# Capacitor_Isolated_Supply.net
KiCad netlist of a schematic drawn in Altium Designer
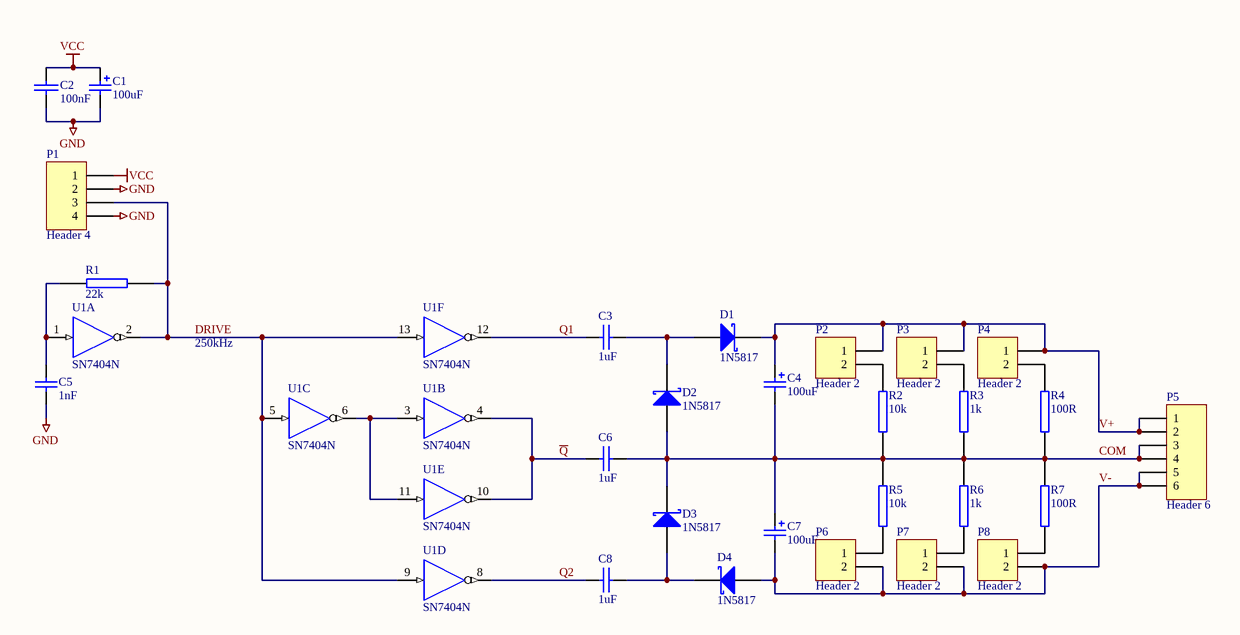
[diagram p0: Capacitor Isolated Supply (Bipolar).SchDoc]

(export (version "E")
  (design (tool "Eeschema 10.0.6"))
  (components
    (comp (ref "C1")
      (value "100uF")
      (footprint "RB5-10.5")
      (description "CAPACITOR POLARISED TAG B CASE")
      (fields
        (field (name "MANUFACTURER") "Generic Components")
        (field (name "MOUSER PART NO.") "74-293D106X9020B8T")
      )
      (libsource (lib "Mi-Call Schematic") (part "Cap Pol"))
    )
    (comp (ref "C2")
      (value "100nF")
      (footprint "CAP (3D) - 0805")
      (description "CAPACITOR SMD 0603")
      (fields (field (name "MOUSER PART NO.") "81-GCM188R71C104KA7D") (field (name "MANUFACTURER") "Murata"))
      (libsource (lib "Mi-Call Schematic") (part "CAP"))
    )
    (comp (ref "C3")
      (value "1uF")
      (footprint "RES (3D) - 1210")
      (description "CAPACITOR SMD 0603")
      (fields (field (name "MOUSER PART NO.") "77-VJ1206V105MXATBC") (field (name "MANUFACTURER") "Vishay"))
      (libsource (lib "Mi-Call Schematic") (part "CAP"))
    )
    (comp (ref "C4")
      (value "100uF")
      (footprint "RB5-10.5")
      (description "CAPACITOR POLARISED TAG B CASE")
      (fields
        (field (name "MANUFACTURER") "Generic Components")
        (field (name "MOUSER PART NO.") "74-293D106X9020B8T")
      )
      (libsource (lib "Mi-Call Schematic") (part "Cap Pol"))
    )
    (comp (ref "C5")
      (value "1nF")
      (footprint "CAP (3D) - 0805")
      (description "Capacitor")
      (fields (field (name "Comment") "Cap") (field (name "PUBLISHER") "Altium Limited"))
      (libsource (lib "Miscellaneous Devices") (part "Cap"))
    )
    (comp (ref "C6")
      (value "1uF")
      (footprint "RES (3D) - 1210")
      (description "CAPACITOR SMD 0603")
      (fields (field (name "MOUSER PART NO.") "77-VJ1206V105MXATBC") (field (name "MANUFACTURER") "Vishay"))
      (libsource (lib "Mi-Call Schematic") (part "CAP"))
    )
    (comp (ref "C7")
      (value "100uF")
      (footprint "RB5-10.5")
      (description "CAPACITOR POLARISED TAG B CASE")
      (fields
        (field (name "MANUFACTURER") "Generic Components")
        (field (name "MOUSER PART NO.") "74-293D106X9020B8T")
      )
      (libsource (lib "Mi-Call Schematic") (part "Cap Pol"))
    )
    (comp (ref "C8")
      (value "1uF")
      (footprint "RES (3D) - 1210")
      (description "CAPACITOR SMD 0603")
      (fields (field (name "MOUSER PART NO.") "77-VJ1206V105MXATBC") (field (name "MANUFACTURER") "Vishay"))
      (libsource (lib "Mi-Call Schematic") (part "CAP"))
    )
    (comp (ref "D1")
      (value "1N5817")
      (footprint "DO-41")
      (description "Schottky Diode")
      (fields (field (name "PUBLISHER") "Altium Limited"))
      (libsource (lib "Miscellaneous Devices") (part "D Schottky"))
    )
    (comp (ref "D2")
      (value "1N5817")
      (footprint "DO-41")
      (description "Schottky Diode")
      (fields (field (name "PUBLISHER") "Altium Limited"))
      (libsource (lib "Miscellaneous Devices") (part "D Schottky"))
    )
    (comp (ref "D3")
      (value "1N5817")
      (footprint "DO-41")
      (description "Schottky Diode")
      (fields (field (name "PUBLISHER") "Altium Limited"))
      (libsource (lib "Miscellaneous Devices") (part "D Schottky"))
    )
    (comp (ref "D4")
      (value "1N5817")
      (footprint "DO-41")
      (description "Schottky Diode")
      (fields (field (name "PUBLISHER") "Altium Limited"))
      (libsource (lib "Miscellaneous Devices") (part "D Schottky"))
    )
    (comp (ref "P1")
      (value "Header 4")
      (footprint "HDR1X4")
      (description "Header, 4-Pin")
      (fields (field (name "PUBLISHER") "Altium Limited"))
      (libsource (lib "Miscellaneous Connectors") (part "Header 4"))
    )
    (comp (ref "P2")
      (value "Header 2")
      (footprint "HDR1X2")
      (description "Header, 2-Pin")
      (fields (field (name "PUBLISHER") "Altium Limited"))
      (libsource (lib "Miscellaneous Connectors") (part "Header 2"))
    )
    (comp (ref "P3")
      (value "Header 2")
      (footprint "HDR1X2")
      (description "Header, 2-Pin")
      (fields (field (name "PUBLISHER") "Altium Limited"))
      (libsource (lib "Miscellaneous Connectors") (part "Header 2"))
    )
    (comp (ref "P4")
      (value "Header 2")
      (footprint "HDR1X2")
      (description "Header, 2-Pin")
      (fields (field (name "PUBLISHER") "Altium Limited"))
      (libsource (lib "Miscellaneous Connectors") (part "Header 2"))
    )
    (comp (ref "P5")
      (value "Header 6")
      (footprint "HDR1X6")
      (description "Header, 6-Pin")
      (fields (field (name "PUBLISHER") "Altium Limited"))
      (libsource (lib "Miscellaneous Connectors") (part "Header 6"))
    )
    (comp (ref "P6")
      (value "Header 2")
      (footprint "HDR1X2")
      (description "Header, 2-Pin")
      (fields (field (name "PUBLISHER") "Altium Limited"))
      (libsource (lib "Miscellaneous Connectors") (part "Header 2"))
    )
    (comp (ref "P7")
      (value "Header 2")
      (footprint "HDR1X2")
      (description "Header, 2-Pin")
      (fields (field (name "PUBLISHER") "Altium Limited"))
      (libsource (lib "Miscellaneous Connectors") (part "Header 2"))
    )
    (comp (ref "P8")
      (value "Header 2")
      (footprint "HDR1X2")
      (description "Header, 2-Pin")
      (fields (field (name "PUBLISHER") "Altium Limited"))
      (libsource (lib "Miscellaneous Connectors") (part "Header 2"))
    )
    (comp (ref "R1")
      (value "22k")
      (footprint "RES (3D) - 0805")
      (description "RESISTOR SMD 0603 10k")
      (libsource (lib "NASCO Resistors") (part "RES SMD 0603 10k"))
    )
    (comp (ref "R2")
      (value "10k")
      (footprint "RES (3D) - 0805")
      (description "RESISTOR SMD 0603 10k")
      (libsource (lib "NASCO Resistors") (part "RES SMD 0603 10k"))
    )
    (comp (ref "R3")
      (value "1k")
      (footprint "RES (3D) - 0805")
      (description "RESISTOR SMD 0603 10k")
      (libsource (lib "NASCO Resistors") (part "RES SMD 0603 10k"))
    )
    (comp (ref "R4")
      (value "100R")
      (footprint "RES (3D) - 0805")
      (description "RESISTOR SMD 0603 10k")
      (libsource (lib "NASCO Resistors") (part "RES SMD 0603 10k"))
    )
    (comp (ref "R5")
      (value "10k")
      (footprint "RES (3D) - 0805")
      (description "RESISTOR SMD 0603 10k")
      (libsource (lib "NASCO Resistors") (part "RES SMD 0603 10k"))
    )
    (comp (ref "R6")
      (value "1k")
      (footprint "RES (3D) - 0805")
      (description "RESISTOR SMD 0603 10k")
      (libsource (lib "NASCO Resistors") (part "RES SMD 0603 10k"))
    )
    (comp (ref "R7")
      (value "100R")
      (footprint "RES (3D) - 0805")
      (description "RESISTOR SMD 0603 10k")
      (libsource (lib "NASCO Resistors") (part "RES SMD 0603 10k"))
    )
    (comp (ref "U1")
      (value "SN7404N")
      (footprint "N014")
      (description "Hex Inverter")
      (fields (field (name "PUBLISHER") "Altium Limited"))
      (libsource (lib "TI Logic Gate 1") (part "SN7404N"))
    )
  )
  (nets
    (net (code "1") (name "/COM") (class "Default")
      (node (ref "C4") (pin "2") (pinfunction "2_2") (pintype "passive"))
      (node (ref "C6") (pin "2") (pinfunction "2_2") (pintype "passive"))
      (node (ref "C7") (pin "1") (pinfunction "1_1") (pintype "passive"))
      (node (ref "D2") (pin "1") (pinfunction "A_1") (pintype "passive"))
      (node (ref "D3") (pin "2") (pinfunction "K_2") (pintype "passive"))
      (node (ref "P5") (pin "3") (pinfunction "3_3") (pintype "passive"))
      (node (ref "P5") (pin "4") (pinfunction "4_4") (pintype "passive"))
      (node (ref "R2") (pin "1") (pinfunction "1_1") (pintype "passive"))
      (node (ref "R3") (pin "1") (pinfunction "1_1") (pintype "passive"))
      (node (ref "R4") (pin "1") (pinfunction "1_1") (pintype "passive"))
      (node (ref "R5") (pin "2") (pinfunction "2_2") (pintype "passive"))
      (node (ref "R6") (pin "2") (pinfunction "2_2") (pintype "passive"))
      (node (ref "R7") (pin "2") (pinfunction "2_2") (pintype "passive"))
    )
    (net (code "2") (name "/DRIVE") (class "Default")
      (node (ref "P1") (pin "3") (pinfunction "3_3") (pintype "passive"))
      (node (ref "R1") (pin "1") (pinfunction "1_1") (pintype "passive"))
      (node (ref "U1") (pin "13") (pinfunction "A_13") (pintype "input"))
      (node (ref "U1") (pin "2") (pinfunction "Y_2") (pintype "output"))
      (node (ref "U1") (pin "5") (pinfunction "A_5") (pintype "input"))
      (node (ref "U1") (pin "9") (pinfunction "A_9") (pintype "input"))
    )
    (net (code "3") (name "/Q1") (class "Default")
      (node (ref "C3") (pin "1") (pinfunction "1_1") (pintype "passive"))
      (node (ref "U1") (pin "12") (pinfunction "Y_12") (pintype "output"))
    )
    (net (code "4") (name "/Q2") (class "Default")
      (node (ref "C8") (pin "1") (pinfunction "1_1") (pintype "passive"))
      (node (ref "U1") (pin "8") (pinfunction "Y_8") (pintype "output"))
    )
    (net (code "5") (name "/V+") (class "Default")
      (node (ref "C4") (pin "1") (pinfunction "1_1") (pintype "passive"))
      (node (ref "D1") (pin "2") (pinfunction "K_2") (pintype "passive"))
      (node (ref "P2") (pin "1") (pinfunction "1_1") (pintype "passive"))
      (node (ref "P3") (pin "1") (pinfunction "1_1") (pintype "passive"))
      (node (ref "P4") (pin "1") (pinfunction "1_1") (pintype "passive"))
      (node (ref "P5") (pin "1") (pinfunction "1_1") (pintype "passive"))
      (node (ref "P5") (pin "2") (pinfunction "2_2") (pintype "passive"))
    )
    (net (code "6") (name "/V-") (class "Default")
      (node (ref "C7") (pin "2") (pinfunction "2_2") (pintype "passive"))
      (node (ref "D4") (pin "1") (pinfunction "A_1") (pintype "passive"))
      (node (ref "P5") (pin "5") (pinfunction "5_5") (pintype "passive"))
      (node (ref "P5") (pin "6") (pinfunction "6_6") (pintype "passive"))
      (node (ref "P6") (pin "2") (pinfunction "2_2") (pintype "passive"))
      (node (ref "P7") (pin "2") (pinfunction "2_2") (pintype "passive"))
      (node (ref "P8") (pin "2") (pinfunction "2_2") (pintype "passive"))
    )
    (net (code "7") (name "/~{Q}") (class "Default")
      (node (ref "C6") (pin "1") (pinfunction "1_1") (pintype "passive"))
      (node (ref "U1") (pin "10") (pinfunction "Y_10") (pintype "output"))
      (node (ref "U1") (pin "4") (pinfunction "Y_4") (pintype "output"))
    )
    (net (code "8") (name "GND") (class "Default")
      (node (ref "C1") (pin "2") (pinfunction "2_2") (pintype "passive"))
      (node (ref "C2") (pin "2") (pinfunction "2_2") (pintype "passive"))
      (node (ref "C5") (pin "2") (pinfunction "2_2") (pintype "passive"))
      (node (ref "P1") (pin "2") (pinfunction "2_2") (pintype "passive"))
      (node (ref "P1") (pin "4") (pinfunction "4_4") (pintype "passive"))
      (node (ref "U1") (pin "7") (pinfunction "GND_7") (pintype "power_in"))
    )
    (net (code "9") (name "Net-(D1-A)") (class "Default")
      (node (ref "C3") (pin "2") (pinfunction "2_2") (pintype "passive"))
      (node (ref "D1") (pin "1") (pinfunction "A_1") (pintype "passive"))
      (node (ref "D2") (pin "2") (pinfunction "K_2") (pintype "passive"))
    )
    (net (code "10") (name "Net-(D3-A)") (class "Default")
      (node (ref "C8") (pin "2") (pinfunction "2_2") (pintype "passive"))
      (node (ref "D3") (pin "1") (pinfunction "A_1") (pintype "passive"))
      (node (ref "D4") (pin "2") (pinfunction "K_2") (pintype "passive"))
    )
    (net (code "11") (name "Net-(P2-Pad2)") (class "Default")
      (node (ref "P2") (pin "2") (pinfunction "2_2") (pintype "passive"))
      (node (ref "R2") (pin "2") (pinfunction "2_2") (pintype "passive"))
    )
    (net (code "12") (name "Net-(P3-Pad2)") (class "Default")
      (node (ref "P3") (pin "2") (pinfunction "2_2") (pintype "passive"))
      (node (ref "R3") (pin "2") (pinfunction "2_2") (pintype "passive"))
    )
    (net (code "13") (name "Net-(P4-Pad2)") (class "Default")
      (node (ref "P4") (pin "2") (pinfunction "2_2") (pintype "passive"))
      (node (ref "R4") (pin "2") (pinfunction "2_2") (pintype "passive"))
    )
    (net (code "14") (name "Net-(P6-Pad1)") (class "Default")
      (node (ref "P6") (pin "1") (pinfunction "1_1") (pintype "passive"))
      (node (ref "R5") (pin "1") (pinfunction "1_1") (pintype "passive"))
    )
    (net (code "15") (name "Net-(P7-Pad1)") (class "Default")
      (node (ref "P7") (pin "1") (pinfunction "1_1") (pintype "passive"))
      (node (ref "R6") (pin "1") (pinfunction "1_1") (pintype "passive"))
    )
    (net (code "16") (name "Net-(P8-Pad1)") (class "Default")
      (node (ref "P8") (pin "1") (pinfunction "1_1") (pintype "passive"))
      (node (ref "R7") (pin "1") (pinfunction "1_1") (pintype "passive"))
    )
    (net (code "17") (name "Net-(U1A-A)") (class "Default")
      (node (ref "C5") (pin "1") (pinfunction "1_1") (pintype "passive"))
      (node (ref "R1") (pin "2") (pinfunction "2_2") (pintype "passive"))
      (node (ref "U1") (pin "1") (pinfunction "A_1") (pintype "input"))
    )
    (net (code "18") (name "Net-(U1B-A)") (class "Default")
      (node (ref "U1") (pin "11") (pinfunction "A_11") (pintype "input"))
      (node (ref "U1") (pin "3") (pinfunction "A_3") (pintype "input"))
      (node (ref "U1") (pin "6") (pinfunction "Y_6") (pintype "output"))
    )
    (net (code "19") (name "VCC") (class "Default")
      (node (ref "C1") (pin "1") (pinfunction "1_1") (pintype "passive"))
      (node (ref "C2") (pin "1") (pinfunction "1_1") (pintype "passive"))
      (node (ref "P1") (pin "1") (pinfunction "1_1") (pintype "passive"))
      (node (ref "U1") (pin "14") (pinfunction "VCC_14") (pintype "power_in"))
    )
  )
)
